# DOT-SHIM.net
KiCad netlist of a schematic drawn in EAGLE
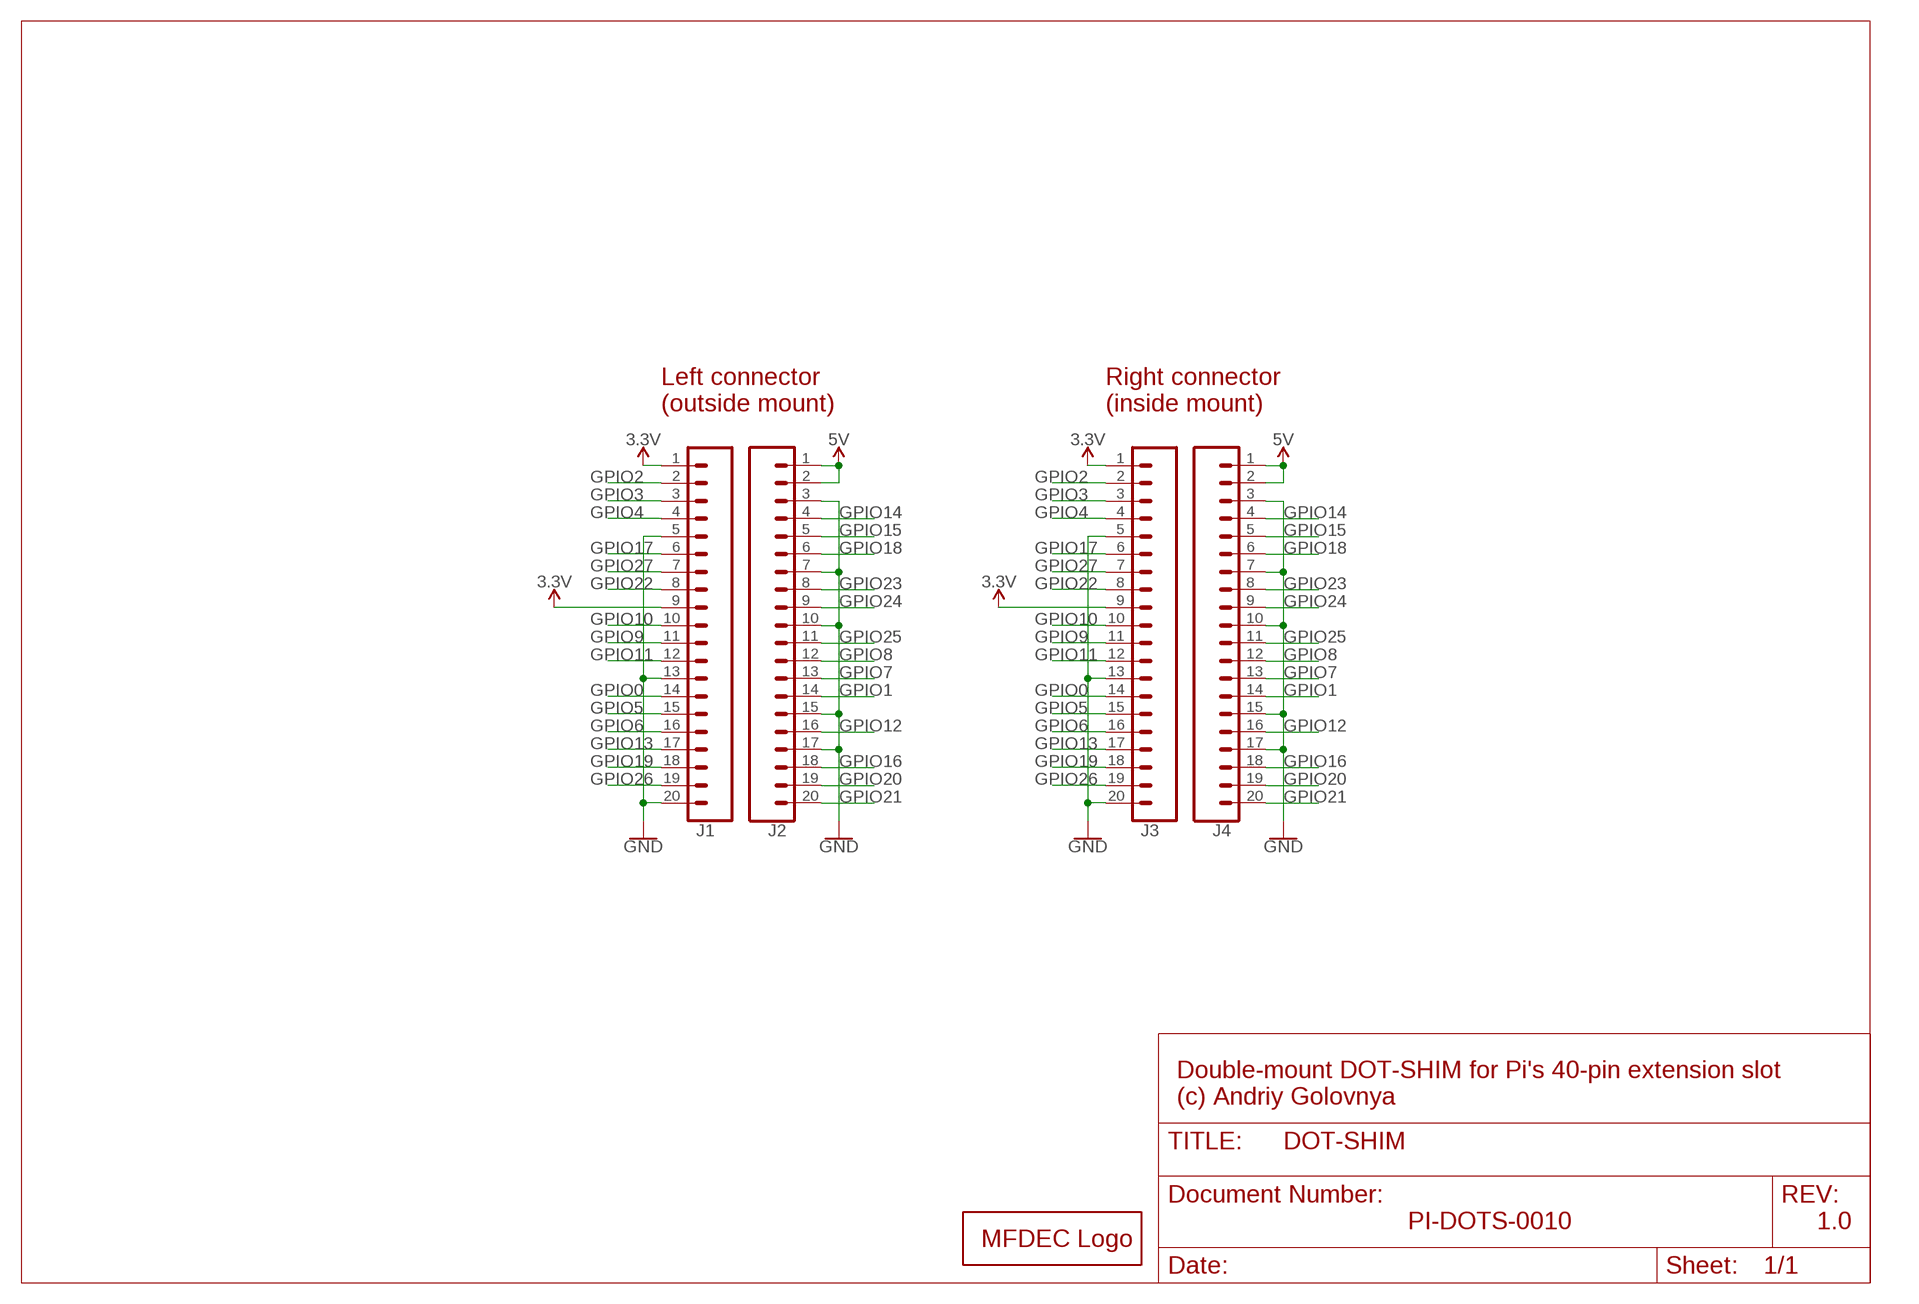
[diagram p0: schematic, sheet 1]

(export (version "E")
  (design (tool "Eeschema 10.0.6"))
  (components
    (comp (ref "J1")
      (value "CONN_20LOCK")
      (footprint "eagle-import:1X20_LOCK")
      (libsource (lib "eagle-import") (part "CONN_20LOCK"))
    )
    (comp (ref "J2")
      (value "CONN_20LOCK")
      (footprint "eagle-import:1X20_LOCK")
      (libsource (lib "eagle-import") (part "CONN_20LOCK"))
    )
    (comp (ref "J3")
      (value "CONN_20LOCK")
      (footprint "eagle-import:1X20_LOCK")
      (libsource (lib "eagle-import") (part "CONN_20LOCK"))
    )
    (comp (ref "J4")
      (value "CONN_20LOCK")
      (footprint "eagle-import:1X20_LOCK")
      (libsource (lib "eagle-import") (part "CONN_20LOCK"))
    )
    (comp (ref "LOGO2")
      (value "MFDECLOGO_L_20MM")
      (footprint "eagle-import:MFDEC_L_20MM")
      (libsource (lib "eagle-import") (part "MFDECLOGO_L_20MM"))
    )
  )
  (nets
    (net (code "1") (name "/GPIO0") (class "Default")
      (node (ref "J1") (pin "14") (pinfunction "14_14") (pintype "passive"))
      (node (ref "J3") (pin "14") (pinfunction "14_14") (pintype "passive"))
    )
    (net (code "2") (name "/GPIO1") (class "Default")
      (node (ref "J2") (pin "14") (pinfunction "14_14") (pintype "passive"))
      (node (ref "J4") (pin "14") (pinfunction "14_14") (pintype "passive"))
    )
    (net (code "3") (name "/GPIO2") (class "Default")
      (node (ref "J1") (pin "2") (pinfunction "2_2") (pintype "passive"))
      (node (ref "J3") (pin "2") (pinfunction "2_2") (pintype "passive"))
    )
    (net (code "4") (name "/GPIO3") (class "Default")
      (node (ref "J1") (pin "3") (pinfunction "3_3") (pintype "passive"))
      (node (ref "J3") (pin "3") (pinfunction "3_3") (pintype "passive"))
    )
    (net (code "5") (name "/GPIO4") (class "Default")
      (node (ref "J1") (pin "4") (pinfunction "4_4") (pintype "passive"))
      (node (ref "J3") (pin "4") (pinfunction "4_4") (pintype "passive"))
    )
    (net (code "6") (name "/GPIO5") (class "Default")
      (node (ref "J1") (pin "15") (pinfunction "15_15") (pintype "passive"))
      (node (ref "J3") (pin "15") (pinfunction "15_15") (pintype "passive"))
    )
    (net (code "7") (name "/GPIO6") (class "Default")
      (node (ref "J1") (pin "16") (pinfunction "16_16") (pintype "passive"))
      (node (ref "J3") (pin "16") (pinfunction "16_16") (pintype "passive"))
    )
    (net (code "8") (name "/GPIO7") (class "Default")
      (node (ref "J2") (pin "13") (pinfunction "13_13") (pintype "passive"))
      (node (ref "J4") (pin "13") (pinfunction "13_13") (pintype "passive"))
    )
    (net (code "9") (name "/GPIO8") (class "Default")
      (node (ref "J2") (pin "12") (pinfunction "12_12") (pintype "passive"))
      (node (ref "J4") (pin "12") (pinfunction "12_12") (pintype "passive"))
    )
    (net (code "10") (name "/GPIO9") (class "Default")
      (node (ref "J1") (pin "11") (pinfunction "11_11") (pintype "passive"))
      (node (ref "J3") (pin "11") (pinfunction "11_11") (pintype "passive"))
    )
    (net (code "11") (name "/GPIO10") (class "Default")
      (node (ref "J1") (pin "10") (pinfunction "10_10") (pintype "passive"))
      (node (ref "J3") (pin "10") (pinfunction "10_10") (pintype "passive"))
    )
    (net (code "12") (name "/GPIO11") (class "Default")
      (node (ref "J1") (pin "12") (pinfunction "12_12") (pintype "passive"))
      (node (ref "J3") (pin "12") (pinfunction "12_12") (pintype "passive"))
    )
    (net (code "13") (name "/GPIO12") (class "Default")
      (node (ref "J2") (pin "16") (pinfunction "16_16") (pintype "passive"))
      (node (ref "J4") (pin "16") (pinfunction "16_16") (pintype "passive"))
    )
    (net (code "14") (name "/GPIO13") (class "Default")
      (node (ref "J1") (pin "17") (pinfunction "17_17") (pintype "passive"))
      (node (ref "J3") (pin "17") (pinfunction "17_17") (pintype "passive"))
    )
    (net (code "15") (name "/GPIO14") (class "Default")
      (node (ref "J2") (pin "4") (pinfunction "4_4") (pintype "passive"))
      (node (ref "J4") (pin "4") (pinfunction "4_4") (pintype "passive"))
    )
    (net (code "16") (name "/GPIO15") (class "Default")
      (node (ref "J2") (pin "5") (pinfunction "5_5") (pintype "passive"))
      (node (ref "J4") (pin "5") (pinfunction "5_5") (pintype "passive"))
    )
    (net (code "17") (name "/GPIO16") (class "Default")
      (node (ref "J2") (pin "18") (pinfunction "18_18") (pintype "passive"))
      (node (ref "J4") (pin "18") (pinfunction "18_18") (pintype "passive"))
    )
    (net (code "18") (name "/GPIO17") (class "Default")
      (node (ref "J1") (pin "6") (pinfunction "6_6") (pintype "passive"))
      (node (ref "J3") (pin "6") (pinfunction "6_6") (pintype "passive"))
    )
    (net (code "19") (name "/GPIO18") (class "Default")
      (node (ref "J2") (pin "6") (pinfunction "6_6") (pintype "passive"))
      (node (ref "J4") (pin "6") (pinfunction "6_6") (pintype "passive"))
    )
    (net (code "20") (name "/GPIO19") (class "Default")
      (node (ref "J1") (pin "18") (pinfunction "18_18") (pintype "passive"))
      (node (ref "J3") (pin "18") (pinfunction "18_18") (pintype "passive"))
    )
    (net (code "21") (name "/GPIO20") (class "Default")
      (node (ref "J2") (pin "19") (pinfunction "19_19") (pintype "passive"))
      (node (ref "J4") (pin "19") (pinfunction "19_19") (pintype "passive"))
    )
    (net (code "22") (name "/GPIO21") (class "Default")
      (node (ref "J2") (pin "20") (pinfunction "20_20") (pintype "passive"))
      (node (ref "J4") (pin "20") (pinfunction "20_20") (pintype "passive"))
    )
    (net (code "23") (name "/GPIO22") (class "Default")
      (node (ref "J1") (pin "8") (pinfunction "8_8") (pintype "passive"))
      (node (ref "J3") (pin "8") (pinfunction "8_8") (pintype "passive"))
    )
    (net (code "24") (name "/GPIO23") (class "Default")
      (node (ref "J2") (pin "8") (pinfunction "8_8") (pintype "passive"))
      (node (ref "J4") (pin "8") (pinfunction "8_8") (pintype "passive"))
    )
    (net (code "25") (name "/GPIO24") (class "Default")
      (node (ref "J2") (pin "9") (pinfunction "9_9") (pintype "passive"))
      (node (ref "J4") (pin "9") (pinfunction "9_9") (pintype "passive"))
    )
    (net (code "26") (name "/GPIO25") (class "Default")
      (node (ref "J2") (pin "11") (pinfunction "11_11") (pintype "passive"))
      (node (ref "J4") (pin "11") (pinfunction "11_11") (pintype "passive"))
    )
    (net (code "27") (name "/GPIO26") (class "Default")
      (node (ref "J1") (pin "19") (pinfunction "19_19") (pintype "passive"))
      (node (ref "J3") (pin "19") (pinfunction "19_19") (pintype "passive"))
    )
    (net (code "28") (name "/GPIO27") (class "Default")
      (node (ref "J1") (pin "7") (pinfunction "7_7") (pintype "passive"))
      (node (ref "J3") (pin "7") (pinfunction "7_7") (pintype "passive"))
    )
    (net (code "29") (name "3.3V") (class "Default")
      (node (ref "J1") (pin "1") (pinfunction "1_1") (pintype "passive"))
      (node (ref "J1") (pin "9") (pinfunction "9_9") (pintype "passive"))
      (node (ref "J3") (pin "1") (pinfunction "1_1") (pintype "passive"))
      (node (ref "J3") (pin "9") (pinfunction "9_9") (pintype "passive"))
    )
    (net (code "30") (name "5V") (class "Default")
      (node (ref "J2") (pin "1") (pinfunction "1_1") (pintype "passive"))
      (node (ref "J2") (pin "2") (pinfunction "2_2") (pintype "passive"))
      (node (ref "J4") (pin "1") (pinfunction "1_1") (pintype "passive"))
      (node (ref "J4") (pin "2") (pinfunction "2_2") (pintype "passive"))
    )
    (net (code "31") (name "GND") (class "Default")
      (node (ref "J1") (pin "13") (pinfunction "13_13") (pintype "passive"))
      (node (ref "J1") (pin "20") (pinfunction "20_20") (pintype "passive"))
      (node (ref "J1") (pin "5") (pinfunction "5_5") (pintype "passive"))
      (node (ref "J2") (pin "10") (pinfunction "10_10") (pintype "passive"))
      (node (ref "J2") (pin "15") (pinfunction "15_15") (pintype "passive"))
      (node (ref "J2") (pin "17") (pinfunction "17_17") (pintype "passive"))
      (node (ref "J2") (pin "3") (pinfunction "3_3") (pintype "passive"))
      (node (ref "J2") (pin "7") (pinfunction "7_7") (pintype "passive"))
      (node (ref "J3") (pin "13") (pinfunction "13_13") (pintype "passive"))
      (node (ref "J3") (pin "20") (pinfunction "20_20") (pintype "passive"))
      (node (ref "J3") (pin "5") (pinfunction "5_5") (pintype "passive"))
      (node (ref "J4") (pin "10") (pinfunction "10_10") (pintype "passive"))
      (node (ref "J4") (pin "15") (pinfunction "15_15") (pintype "passive"))
      (node (ref "J4") (pin "17") (pinfunction "17_17") (pintype "passive"))
      (node (ref "J4") (pin "3") (pinfunction "3_3") (pintype "passive"))
      (node (ref "J4") (pin "7") (pinfunction "7_7") (pintype "passive"))
    )
  )
)
